# Minimotor.net
KiCad netlist of a schematic drawn in EAGLE
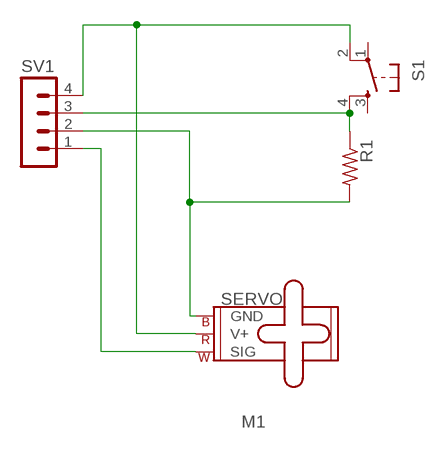
[diagram p0: schematic, sheet 1]

(export (version "E")
  (design (tool "Eeschema 10.0.6"))
  (components
    (comp (ref "M1")
      (value "SERVO")
      (footprint "eagle-import:1X03")
      (libsource (lib "eagle-import") (part "SERVO"))
    )
    (comp (ref "R1")
      (value "R-US_0204/7")
      (footprint "eagle-import:0204_7")
      (libsource (lib "eagle-import") (part "R-US_0204/7"))
    )
    (comp (ref "S1")
      (value "TAC_SWITCHPTH")
      (footprint "eagle-import:TACTILE-PTH")
      (libsource (lib "eagle-import") (part "TAC_SWITCHPTH"))
    )
    (comp (ref "SV1")
      (value "MA04-1")
      (footprint "eagle-import:MA04-1")
      (libsource (lib "eagle-import") (part "MA04-1"))
    )
  )
  (nets
    (net (code "1") (name "Net-(M1-GND)") (class "Default")
      (node (ref "M1") (pin "3") (pinfunction "GND_3") (pintype "bidirectional"))
      (node (ref "R1") (pin "2") (pinfunction "2_2") (pintype "passive"))
      (node (ref "SV1") (pin "2") (pinfunction "2_2") (pintype "passive"))
    )
    (net (code "2") (name "Net-(M1-SIG)") (class "Default")
      (node (ref "M1") (pin "1") (pinfunction "SIG_1") (pintype "bidirectional"))
      (node (ref "SV1") (pin "1") (pinfunction "1_1") (pintype "passive"))
    )
    (net (code "3") (name "Net-(M1-V+)") (class "Default")
      (node (ref "M1") (pin "2") (pinfunction "V+_2") (pintype "bidirectional"))
      (node (ref "S1") (pin "2") (pinfunction "2_2") (pintype "passive"))
      (node (ref "SV1") (pin "4") (pinfunction "4_4") (pintype "passive"))
    )
    (net (code "4") (name "Net-(R1-Pad1)") (class "Default")
      (node (ref "R1") (pin "1") (pinfunction "1_1") (pintype "passive"))
      (node (ref "S1") (pin "4") (pinfunction "4_4") (pintype "passive"))
      (node (ref "SV1") (pin "3") (pinfunction "3_3") (pintype "passive"))
    )
    (net (code "5") (name "unconnected-(S1-Pad1)") (class "Default")
      (node (ref "S1") (pin "1") (pinfunction "1_1") (pintype "passive"))
    )
    (net (code "6") (name "unconnected-(S1-Pad3)") (class "Default")
      (node (ref "S1") (pin "3") (pinfunction "3_3") (pintype "passive"))
    )
  )
)
